# CanBus-Gartensteuerung.net
KiCad netlist of a schematic drawn in EAGLE
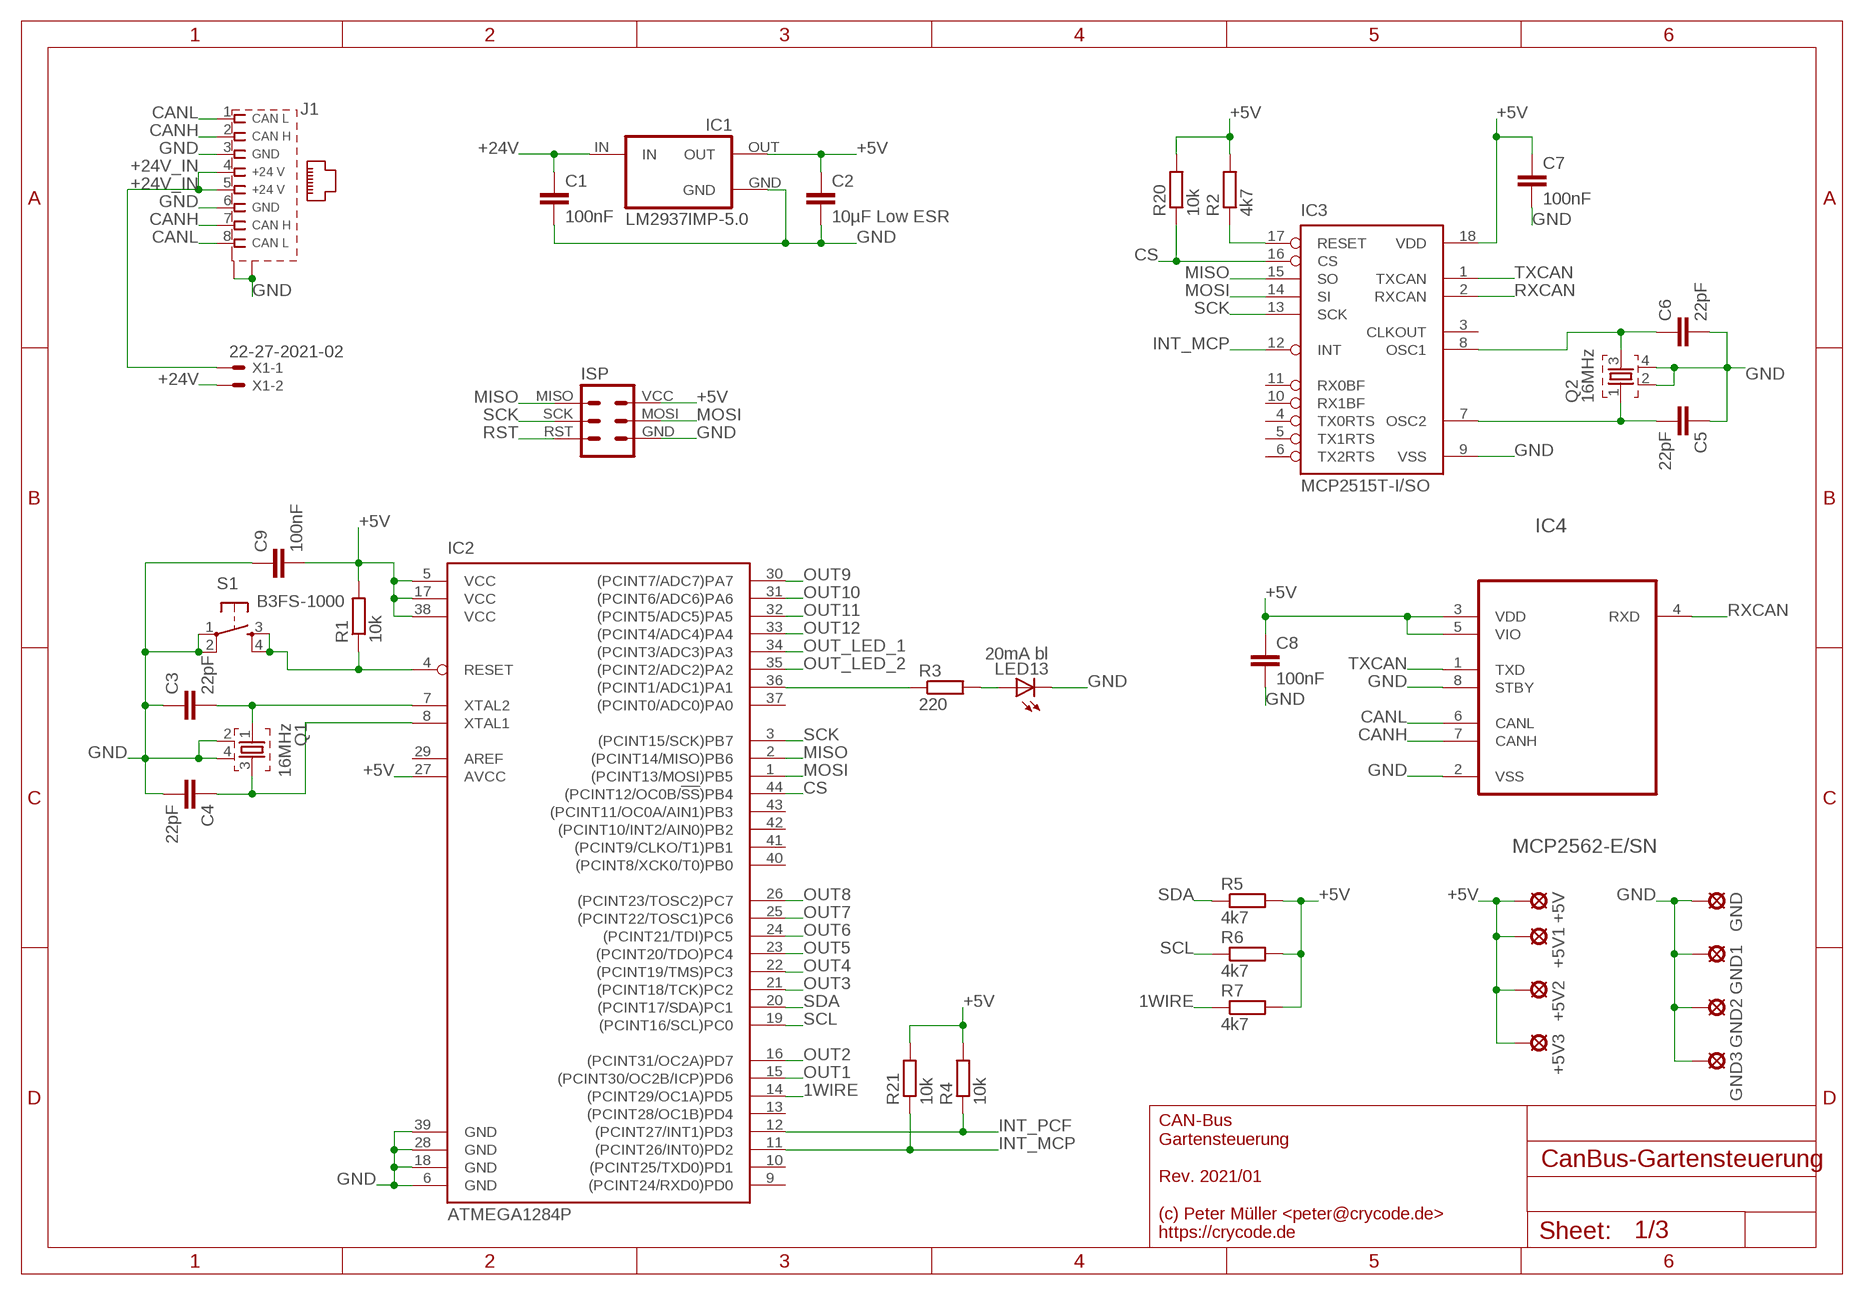
[diagram p0: schematic, sheet 1]
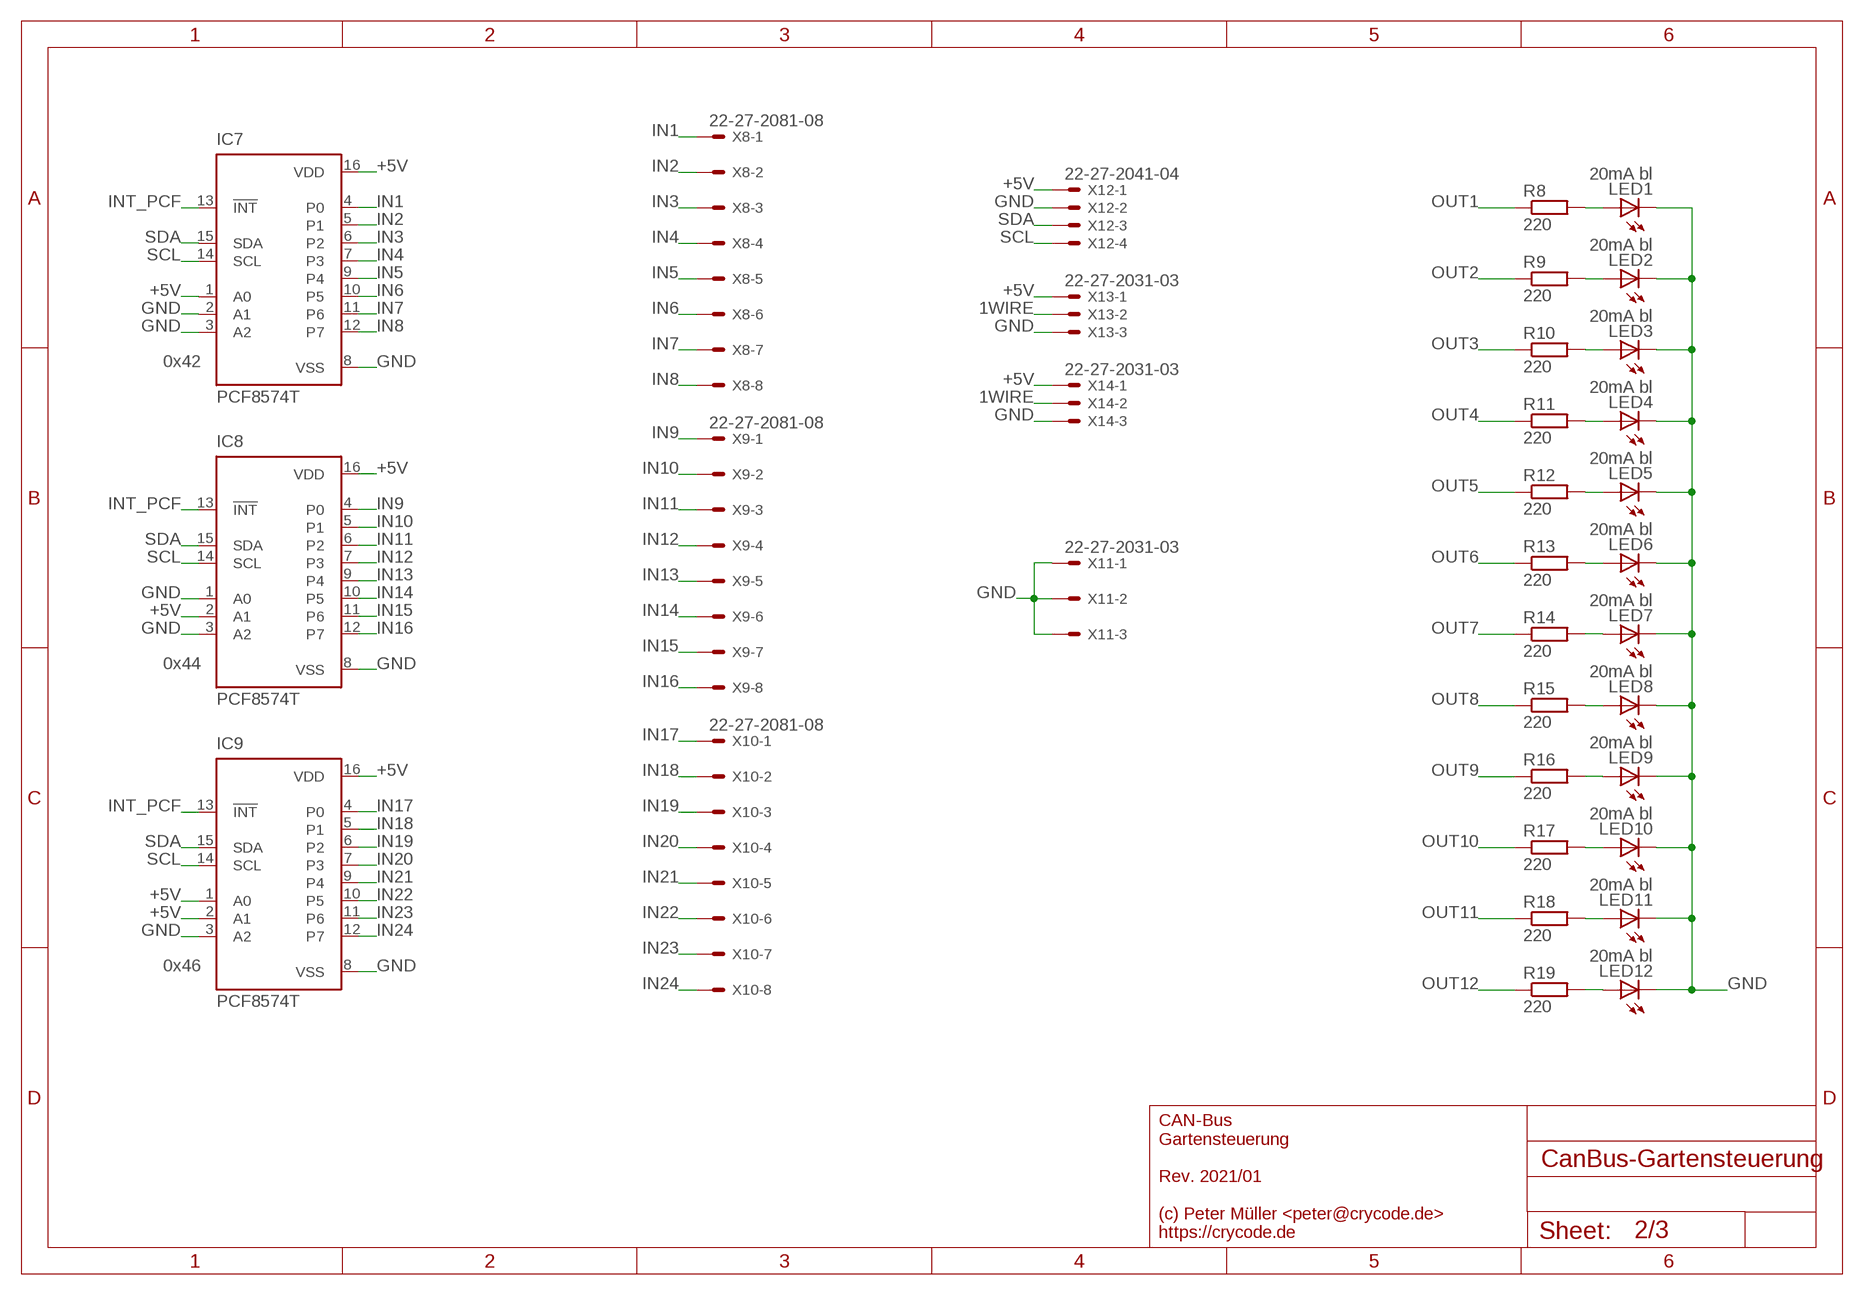
[diagram p1: schematic, sheet 2]
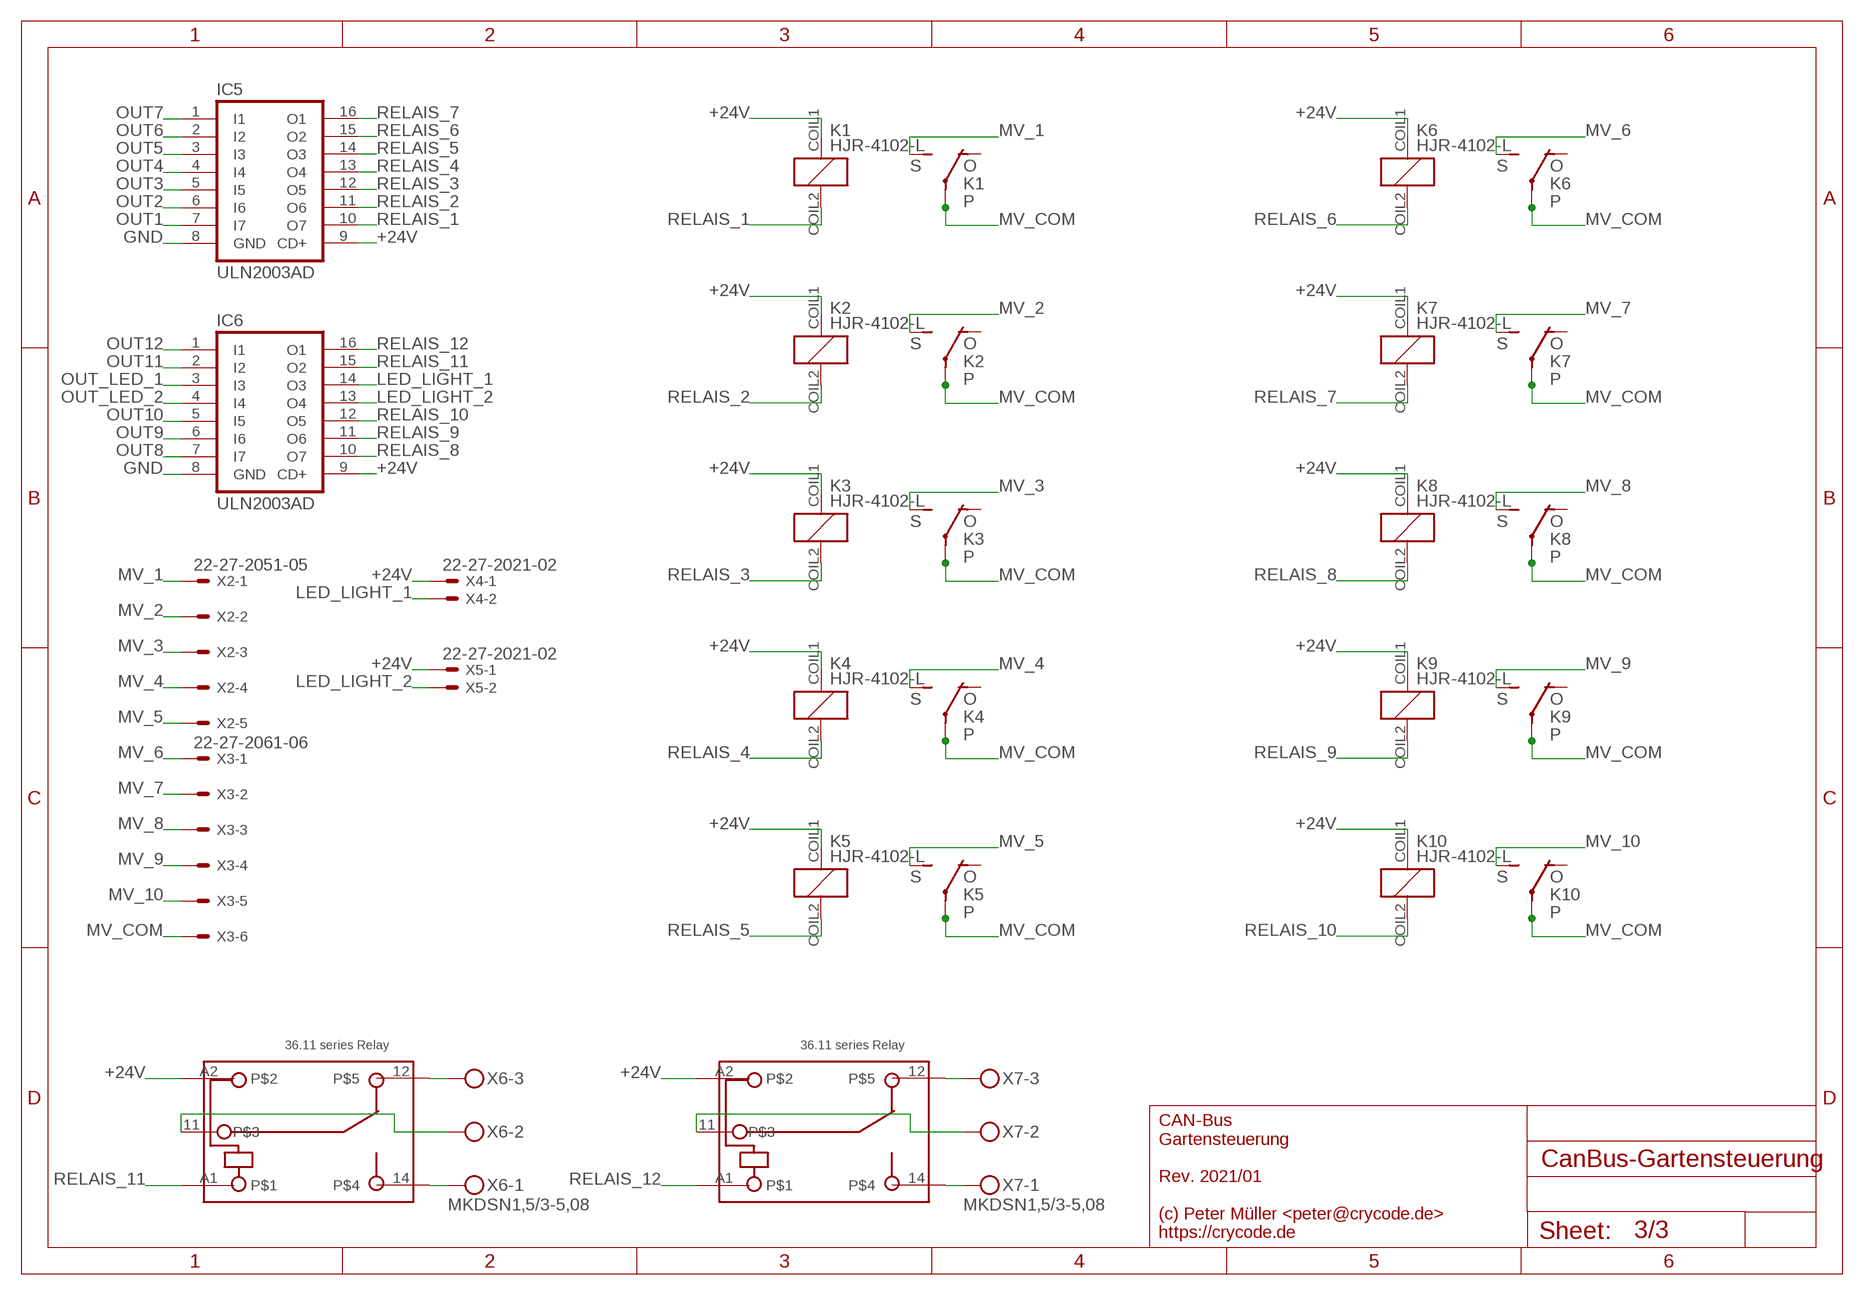
[diagram p2: schematic, sheet 3]

(export (version "E")
  (design (tool "Eeschema 10.0.6"))
  (components
    (comp (ref "+5V")
      (value "LSP13")
      (footprint "eagle-import:LSP13")
      (libsource (lib "eagle-import") (part "LSP13"))
    )
    (comp (ref "+5V1")
      (value "LSP13")
      (footprint "eagle-import:LSP13")
      (libsource (lib "eagle-import") (part "LSP13"))
    )
    (comp (ref "+5V2")
      (value "LSP13")
      (footprint "eagle-import:LSP13")
      (libsource (lib "eagle-import") (part "LSP13"))
    )
    (comp (ref "+5V3")
      (value "LSP13")
      (footprint "eagle-import:LSP13")
      (libsource (lib "eagle-import") (part "LSP13"))
    )
    (comp (ref "C1")
      (value "100nF")
      (footprint "eagle-import:C0805")
      (libsource (lib "eagle-import") (part "C-EUC0805"))
    )
    (comp (ref "C2")
      (value "10µF Low ESR")
      (footprint "eagle-import:C0805")
      (libsource (lib "eagle-import") (part "C-EUC0805"))
    )
    (comp (ref "C3")
      (value "22pF")
      (footprint "eagle-import:C0805")
      (libsource (lib "eagle-import") (part "C-EUC0805"))
    )
    (comp (ref "C4")
      (value "22pF")
      (footprint "eagle-import:C0805")
      (libsource (lib "eagle-import") (part "C-EUC0805"))
    )
    (comp (ref "C5")
      (value "22pF")
      (footprint "eagle-import:C0805")
      (libsource (lib "eagle-import") (part "C-EUC0805"))
    )
    (comp (ref "C6")
      (value "22pF")
      (footprint "eagle-import:C0805")
      (libsource (lib "eagle-import") (part "C-EUC0805"))
    )
    (comp (ref "C7")
      (value "100nF")
      (footprint "eagle-import:C0805")
      (libsource (lib "eagle-import") (part "C-EUC0805"))
    )
    (comp (ref "C8")
      (value "100nF")
      (footprint "eagle-import:C0805")
      (libsource (lib "eagle-import") (part "C-EUC0805"))
    )
    (comp (ref "C9")
      (value "100nF")
      (footprint "eagle-import:C0805")
      (libsource (lib "eagle-import") (part "C-EUC0805"))
    )
    (comp (ref "GND")
      (value "LSP13")
      (footprint "eagle-import:LSP13")
      (libsource (lib "eagle-import") (part "LSP13"))
    )
    (comp (ref "GND1")
      (value "LSP13")
      (footprint "eagle-import:LSP13")
      (libsource (lib "eagle-import") (part "LSP13"))
    )
    (comp (ref "GND2")
      (value "LSP13")
      (footprint "eagle-import:LSP13")
      (libsource (lib "eagle-import") (part "LSP13"))
    )
    (comp (ref "GND3")
      (value "LSP13")
      (footprint "eagle-import:LSP13")
      (libsource (lib "eagle-import") (part "LSP13"))
    )
    (comp (ref "IC1")
      (value "LM2937IMP-5.0")
      (footprint "eagle-import:SOT223")
      (libsource (lib "eagle-import") (part "LM2937IMP-5.0"))
    )
    (comp (ref "IC2")
      (value "ATMEGA1284P")
      (footprint "eagle-import:TQFP44")
      (fields (field (name "MPN") "ATMEGA644PV-10AU"))
      (libsource (lib "eagle-import") (part "ATMEGA644A"))
    )
    (comp (ref "IC3")
      (value "MCP2515T-I/SO")
      (footprint "eagle-import:SO18L")
      (libsource (lib "eagle-import") (part "MCP2515T-I/SO"))
    )
    (comp (ref "IC4")
      (value "MCP2562-E/SN")
      (footprint "eagle-import:SO08")
      (libsource (lib "eagle-import") (part "MCP2562-E/SN"))
    )
    (comp (ref "ISP")
      (value "ISPVIAS-ONLY-1.27MM")
      (footprint "eagle-import:ISP-VIAS-ONLY-1.27MM")
      (libsource (lib "eagle-import") (part "ISPVIAS-ONLY-1.27MM"))
    )
    (comp (ref "J1")
      (value "RJ45-CAN")
      (footprint "eagle-import:MEBP_8-8G")
      (libsource (lib "eagle-import") (part "RJ45-CAN"))
    )
    (comp (ref "LED13")
      (value "20mA bl")
      (footprint "eagle-import:CHIPLED_0805")
      (libsource (lib "eagle-import") (part "LEDCHIPLED_0805"))
    )
    (comp (ref "Q1")
      (value "16MHz")
      (footprint "eagle-import:MJ-5X3.2")
      (libsource (lib "eagle-import") (part "EUROQUARTZ-MMJ"))
    )
    (comp (ref "Q2")
      (value "16MHz")
      (footprint "eagle-import:MJ-5X3.2")
      (libsource (lib "eagle-import") (part "EUROQUARTZ-MMJ"))
    )
    (comp (ref "R1")
      (value "10k")
      (footprint "eagle-import:R0805")
      (libsource (lib "eagle-import") (part "R-EU_R0805"))
    )
    (comp (ref "R2")
      (value "4k7")
      (footprint "eagle-import:R0805")
      (libsource (lib "eagle-import") (part "R-EU_R0805"))
    )
    (comp (ref "R3")
      (value "220")
      (footprint "eagle-import:R0805")
      (libsource (lib "eagle-import") (part "R-EU_R0805"))
    )
    (comp (ref "R4")
      (value "10k")
      (footprint "eagle-import:R0805")
      (libsource (lib "eagle-import") (part "R-EU_R0805"))
    )
    (comp (ref "R5")
      (value "4k7")
      (footprint "eagle-import:R0805")
      (libsource (lib "eagle-import") (part "R-EU_R0805"))
    )
    (comp (ref "R6")
      (value "4k7")
      (footprint "eagle-import:R0805")
      (libsource (lib "eagle-import") (part "R-EU_R0805"))
    )
    (comp (ref "R7")
      (value "4k7")
      (footprint "eagle-import:R0805")
      (libsource (lib "eagle-import") (part "R-EU_R0805"))
    )
    (comp (ref "R20")
      (value "10k")
      (footprint "eagle-import:R0805")
      (libsource (lib "eagle-import") (part "R-EU_R0805"))
    )
    (comp (ref "R21")
      (value "10k")
      (footprint "eagle-import:R0805")
      (libsource (lib "eagle-import") (part "R-EU_R0805"))
    )
    (comp (ref "S1")
      (value "B3FS-1000")
      (footprint "eagle-import:B3FS-1000")
      (libsource (lib "eagle-import") (part "B3FS-1000"))
    )
    (comp (ref "X1")
      (value "22-27-2021-02")
      (footprint "eagle-import:6410-02")
      (libsource (lib "eagle-import") (part "22-?-0227-2021"))
    )
    (comp (ref "IC5")
      (value "ULN2003AD")
      (footprint "eagle-import:SO16")
      (libsource (lib "eagle-import") (part "ULN2003AD"))
    )
    (comp (ref "IC6")
      (value "ULN2003AD")
      (footprint "eagle-import:SO16")
      (libsource (lib "eagle-import") (part "ULN2003AD"))
    )
    (comp (ref "K1")
      (value "HJR-4102-L")
      (footprint "eagle-import:HJR4102")
      (libsource (lib "eagle-import") (part "HJR-4102-L"))
    )
    (comp (ref "K2")
      (value "HJR-4102-L")
      (footprint "eagle-import:HJR4102")
      (libsource (lib "eagle-import") (part "HJR-4102-L"))
    )
    (comp (ref "K3")
      (value "HJR-4102-L")
      (footprint "eagle-import:HJR4102")
      (libsource (lib "eagle-import") (part "HJR-4102-L"))
    )
    (comp (ref "K4")
      (value "HJR-4102-L")
      (footprint "eagle-import:HJR4102")
      (libsource (lib "eagle-import") (part "HJR-4102-L"))
    )
    (comp (ref "K5")
      (value "HJR-4102-L")
      (footprint "eagle-import:HJR4102")
      (libsource (lib "eagle-import") (part "HJR-4102-L"))
    )
    (comp (ref "K6")
      (value "HJR-4102-L")
      (footprint "eagle-import:HJR4102")
      (libsource (lib "eagle-import") (part "HJR-4102-L"))
    )
    (comp (ref "K7")
      (value "HJR-4102-L")
      (footprint "eagle-import:HJR4102")
      (libsource (lib "eagle-import") (part "HJR-4102-L"))
    )
    (comp (ref "K8")
      (value "HJR-4102-L")
      (footprint "eagle-import:HJR4102")
      (libsource (lib "eagle-import") (part "HJR-4102-L"))
    )
    (comp (ref "K9")
      (value "HJR-4102-L")
      (footprint "eagle-import:HJR4102")
      (libsource (lib "eagle-import") (part "HJR-4102-L"))
    )
    (comp (ref "K10")
      (value "HJR-4102-L")
      (footprint "eagle-import:HJR4102")
      (libsource (lib "eagle-import") (part "HJR-4102-L"))
    )
    (comp (ref "K11")
      (value "36.11")
      (footprint "eagle-import:36.11")
      (libsource (lib "eagle-import") (part "36.11"))
    )
    (comp (ref "K12")
      (value "36.11")
      (footprint "eagle-import:36.11")
      (libsource (lib "eagle-import") (part "36.11"))
    )
    (comp (ref "X2")
      (value "22-27-2051-05")
      (footprint "eagle-import:6410-05")
      (libsource (lib "eagle-import") (part "22-?-0527-2051"))
    )
    (comp (ref "X3")
      (value "22-27-2061-06")
      (footprint "eagle-import:6410-06")
      (libsource (lib "eagle-import") (part "22-?-0627-2061"))
    )
    (comp (ref "X4")
      (value "22-27-2021-02")
      (footprint "eagle-import:6410-02")
      (libsource (lib "eagle-import") (part "22-?-0227-2021"))
    )
    (comp (ref "X5")
      (value "22-27-2021-02")
      (footprint "eagle-import:6410-02")
      (libsource (lib "eagle-import") (part "22-?-0227-2021"))
    )
    (comp (ref "X6")
      (value "MKDSN1,5/3-5,08")
      (footprint "eagle-import:MKDSN1,5_3-5,08")
      (libsource (lib "eagle-import") (part "MKDSN1,5/3-5,08"))
    )
    (comp (ref "X7")
      (value "MKDSN1,5/3-5,08")
      (footprint "eagle-import:MKDSN1,5_3-5,08")
      (libsource (lib "eagle-import") (part "MKDSN1,5/3-5,08"))
    )
    (comp (ref "IC7")
      (value "PCF8574T")
      (footprint "eagle-import:SO16W")
      (fields (field (name "MPN") "PCF8574T/3,512"))
      (libsource (lib "eagle-import") (part "PCF8574T"))
    )
    (comp (ref "IC8")
      (value "PCF8574T")
      (footprint "eagle-import:SO16W")
      (fields (field (name "MPN") "PCF8574T/3,512"))
      (libsource (lib "eagle-import") (part "PCF8574T"))
    )
    (comp (ref "IC9")
      (value "PCF8574T")
      (footprint "eagle-import:SO16W")
      (fields (field (name "MPN") "PCF8574T/3,512"))
      (libsource (lib "eagle-import") (part "PCF8574T"))
    )
    (comp (ref "LED1")
      (value "20mA bl")
      (footprint "eagle-import:CHIPLED_0805")
      (libsource (lib "eagle-import") (part "LEDCHIPLED_0805"))
    )
    (comp (ref "LED2")
      (value "20mA bl")
      (footprint "eagle-import:CHIPLED_0805")
      (libsource (lib "eagle-import") (part "LEDCHIPLED_0805"))
    )
    (comp (ref "LED3")
      (value "20mA bl")
      (footprint "eagle-import:CHIPLED_0805")
      (libsource (lib "eagle-import") (part "LEDCHIPLED_0805"))
    )
    (comp (ref "LED4")
      (value "20mA bl")
      (footprint "eagle-import:CHIPLED_0805")
      (libsource (lib "eagle-import") (part "LEDCHIPLED_0805"))
    )
    (comp (ref "LED5")
      (value "20mA bl")
      (footprint "eagle-import:CHIPLED_0805")
      (libsource (lib "eagle-import") (part "LEDCHIPLED_0805"))
    )
    (comp (ref "LED6")
      (value "20mA bl")
      (footprint "eagle-import:CHIPLED_0805")
      (libsource (lib "eagle-import") (part "LEDCHIPLED_0805"))
    )
    (comp (ref "LED7")
      (value "20mA bl")
      (footprint "eagle-import:CHIPLED_0805")
      (libsource (lib "eagle-import") (part "LEDCHIPLED_0805"))
    )
    (comp (ref "LED8")
      (value "20mA bl")
      (footprint "eagle-import:CHIPLED_0805")
      (libsource (lib "eagle-import") (part "LEDCHIPLED_0805"))
    )
    (comp (ref "LED9")
      (value "20mA bl")
      (footprint "eagle-import:CHIPLED_0805")
      (libsource (lib "eagle-import") (part "LEDCHIPLED_0805"))
    )
    (comp (ref "LED10")
      (value "20mA bl")
      (footprint "eagle-import:CHIPLED_0805")
      (libsource (lib "eagle-import") (part "LEDCHIPLED_0805"))
    )
    (comp (ref "LED11")
      (value "20mA bl")
      (footprint "eagle-import:CHIPLED_0805")
      (libsource (lib "eagle-import") (part "LEDCHIPLED_0805"))
    )
    (comp (ref "LED12")
      (value "20mA bl")
      (footprint "eagle-import:CHIPLED_0805")
      (libsource (lib "eagle-import") (part "LEDCHIPLED_0805"))
    )
    (comp (ref "R8")
      (value "220")
      (footprint "eagle-import:R0805")
      (libsource (lib "eagle-import") (part "R-EU_R0805"))
    )
    (comp (ref "R9")
      (value "220")
      (footprint "eagle-import:R0805")
      (libsource (lib "eagle-import") (part "R-EU_R0805"))
    )
    (comp (ref "R10")
      (value "220")
      (footprint "eagle-import:R0805")
      (libsource (lib "eagle-import") (part "R-EU_R0805"))
    )
    (comp (ref "R11")
      (value "220")
      (footprint "eagle-import:R0805")
      (libsource (lib "eagle-import") (part "R-EU_R0805"))
    )
    (comp (ref "R12")
      (value "220")
      (footprint "eagle-import:R0805")
      (libsource (lib "eagle-import") (part "R-EU_R0805"))
    )
    (comp (ref "R13")
      (value "220")
      (footprint "eagle-import:R0805")
      (libsource (lib "eagle-import") (part "R-EU_R0805"))
    )
    (comp (ref "R14")
      (value "220")
      (footprint "eagle-import:R0805")
      (libsource (lib "eagle-import") (part "R-EU_R0805"))
    )
    (comp (ref "R15")
      (value "220")
      (footprint "eagle-import:R0805")
      (libsource (lib "eagle-import") (part "R-EU_R0805"))
    )
    (comp (ref "R16")
      (value "220")
      (footprint "eagle-import:R0805")
      (libsource (lib "eagle-import") (part "R-EU_R0805"))
    )
    (comp (ref "R17")
      (value "220")
      (footprint "eagle-import:R0805")
      (libsource (lib "eagle-import") (part "R-EU_R0805"))
    )
    (comp (ref "R18")
      (value "220")
      (footprint "eagle-import:R0805")
      (libsource (lib "eagle-import") (part "R-EU_R0805"))
    )
    (comp (ref "R19")
      (value "220")
      (footprint "eagle-import:R0805")
      (libsource (lib "eagle-import") (part "R-EU_R0805"))
    )
    (comp (ref "X8")
      (value "22-27-2081-08")
      (footprint "eagle-import:6410-08")
      (libsource (lib "eagle-import") (part "22-?-0827-2081"))
    )
    (comp (ref "X9")
      (value "22-27-2081-08")
      (footprint "eagle-import:6410-08")
      (libsource (lib "eagle-import") (part "22-?-0827-2081"))
    )
    (comp (ref "X10")
      (value "22-27-2081-08")
      (footprint "eagle-import:6410-08")
      (libsource (lib "eagle-import") (part "22-?-0827-2081"))
    )
    (comp (ref "X11")
      (value "22-27-2031-03")
      (footprint "eagle-import:6410-03")
      (libsource (lib "eagle-import") (part "22-?-0327-2031"))
    )
    (comp (ref "X12")
      (value "22-27-2041-04")
      (footprint "eagle-import:6410-04")
      (libsource (lib "eagle-import") (part "22-?-0427-2041"))
    )
    (comp (ref "X13")
      (value "22-27-2031-03")
      (footprint "eagle-import:6410-03")
      (libsource (lib "eagle-import") (part "22-?-0327-2031"))
    )
    (comp (ref "X14")
      (value "22-27-2031-03")
      (footprint "eagle-import:6410-03")
      (libsource (lib "eagle-import") (part "22-?-0327-2031"))
    )
  )
  (nets
    (net (code "1") (name "+5V") (class "Default")
      (node (ref "+5V") (pin "MP") (pinfunction "MP_MP") (pintype "passive"))
      (node (ref "+5V1") (pin "MP") (pinfunction "MP_MP") (pintype "passive"))
      (node (ref "+5V2") (pin "MP") (pinfunction "MP_MP") (pintype "passive"))
      (node (ref "+5V3") (pin "MP") (pinfunction "MP_MP") (pintype "passive"))
      (node (ref "C2") (pin "1") (pinfunction "1_1") (pintype "passive"))
      (node (ref "C7") (pin "1") (pinfunction "1_1") (pintype "passive"))
      (node (ref "C8") (pin "1") (pinfunction "1_1") (pintype "passive"))
      (node (ref "C9") (pin "2") (pinfunction "2_2") (pintype "passive"))
      (node (ref "IC1") (pin "OUT") (pinfunction "OUT_OUT") (pintype "output"))
      (node (ref "IC2") (pin "17") (pinfunction "VCC_17") (pintype "power_in"))
      (node (ref "IC2") (pin "27") (pinfunction "AVCC_27") (pintype "power_in"))
      (node (ref "IC2") (pin "38") (pinfunction "VCC_38") (pintype "power_in"))
      (node (ref "IC2") (pin "5") (pinfunction "VCC_5") (pintype "power_in"))
      (node (ref "IC3") (pin "18") (pinfunction "VDD_18") (pintype "power_in"))
      (node (ref "IC4") (pin "3") (pinfunction "VDD_3") (pintype "power_in"))
      (node (ref "IC4") (pin "5") (pinfunction "VIO_5") (pintype "power_in"))
      (node (ref "IC7") (pin "1") (pinfunction "A0_1") (pintype "input"))
      (node (ref "IC7") (pin "16") (pinfunction "VDD_16") (pintype "power_in"))
      (node (ref "IC8") (pin "16") (pinfunction "VDD_16") (pintype "power_in"))
      (node (ref "IC8") (pin "2") (pinfunction "A1_2") (pintype "input"))
      (node (ref "IC9") (pin "1") (pinfunction "A0_1") (pintype "input"))
      (node (ref "IC9") (pin "16") (pinfunction "VDD_16") (pintype "power_in"))
      (node (ref "IC9") (pin "2") (pinfunction "A1_2") (pintype "input"))
      (node (ref "ISP") (pin "VCC") (pinfunction "VCC_VCC") (pintype "passive"))
      (node (ref "R1") (pin "2") (pinfunction "2_2") (pintype "passive"))
      (node (ref "R2") (pin "2") (pinfunction "2_2") (pintype "passive"))
      (node (ref "R20") (pin "2") (pinfunction "2_2") (pintype "passive"))
      (node (ref "R21") (pin "2") (pinfunction "2_2") (pintype "passive"))
      (node (ref "R4") (pin "2") (pinfunction "2_2") (pintype "passive"))
      (node (ref "R5") (pin "2") (pinfunction "2_2") (pintype "passive"))
      (node (ref "R6") (pin "2") (pinfunction "2_2") (pintype "passive"))
      (node (ref "R7") (pin "2") (pinfunction "2_2") (pintype "passive"))
      (node (ref "X12") (pin "1") (pinfunction "S_1") (pintype "passive"))
      (node (ref "X13") (pin "1") (pinfunction "S_1") (pintype "passive"))
      (node (ref "X14") (pin "1") (pinfunction "S_1") (pintype "passive"))
    )
    (net (code "2") (name "+24V") (class "Default")
      (node (ref "C1") (pin "1") (pinfunction "1_1") (pintype "passive"))
      (node (ref "IC1") (pin "IN") (pinfunction "IN_IN") (pintype "input"))
      (node (ref "IC5") (pin "9") (pinfunction "CD+_9") (pintype "passive"))
      (node (ref "IC6") (pin "9") (pinfunction "CD+_9") (pintype "passive"))
      (node (ref "K1") (pin "COIL1") (pinfunction "1_COIL1") (pintype "passive"))
      (node (ref "K10") (pin "COIL1") (pinfunction "1_COIL1") (pintype "passive"))
      (node (ref "K11") (pin "A2") (pinfunction "P$2_A2") (pintype "passive"))
      (node (ref "K12") (pin "A2") (pinfunction "P$2_A2") (pintype "passive"))
      (node (ref "K2") (pin "COIL1") (pinfunction "1_COIL1") (pintype "passive"))
      (node (ref "K3") (pin "COIL1") (pinfunction "1_COIL1") (pintype "passive"))
      (node (ref "K4") (pin "COIL1") (pinfunction "1_COIL1") (pintype "passive"))
      (node (ref "K5") (pin "COIL1") (pinfunction "1_COIL1") (pintype "passive"))
      (node (ref "K6") (pin "COIL1") (pinfunction "1_COIL1") (pintype "passive"))
      (node (ref "K7") (pin "COIL1") (pinfunction "1_COIL1") (pintype "passive"))
      (node (ref "K8") (pin "COIL1") (pinfunction "1_COIL1") (pintype "passive"))
      (node (ref "K9") (pin "COIL1") (pinfunction "1_COIL1") (pintype "passive"))
      (node (ref "X1") (pin "2") (pinfunction "S_2") (pintype "passive"))
      (node (ref "X4") (pin "1") (pinfunction "S_1") (pintype "passive"))
      (node (ref "X5") (pin "1") (pinfunction "S_1") (pintype "passive"))
    )
    (net (code "3") (name "+24V_IN") (class "Default")
      (node (ref "J1") (pin "4") (pinfunction "4_4") (pintype "passive"))
      (node (ref "J1") (pin "5") (pinfunction "5_5") (pintype "passive"))
      (node (ref "X1") (pin "1") (pinfunction "S_1") (pintype "passive"))
    )
    (net (code "4") (name "1WIRE") (class "Default")
      (node (ref "IC2") (pin "14") (pinfunction "(PCINT29/OC1A)PD5_14") (pintype "bidirectional"))
      (node (ref "R7") (pin "1") (pinfunction "1_1") (pintype "passive"))
      (node (ref "X13") (pin "2") (pinfunction "S_2") (pintype "passive"))
      (node (ref "X14") (pin "2") (pinfunction "S_2") (pintype "passive"))
    )
    (net (code "5") (name "CANH") (class "Default")
      (node (ref "IC4") (pin "7") (pinfunction "CANH_7") (pintype "bidirectional"))
      (node (ref "J1") (pin "2") (pinfunction "2_2") (pintype "passive"))
      (node (ref "J1") (pin "7") (pinfunction "7_7") (pintype "passive"))
    )
    (net (code "6") (name "CANL") (class "Default")
      (node (ref "IC4") (pin "6") (pinfunction "CANL_6") (pintype "bidirectional"))
      (node (ref "J1") (pin "1") (pinfunction "1_1") (pintype "passive"))
      (node (ref "J1") (pin "8") (pinfunction "8_8") (pintype "passive"))
    )
    (net (code "7") (name "CS") (class "Default")
      (node (ref "IC2") (pin "44") (pinfunction "(PCINT12/OC0B/~{SS})PB4_44") (pintype "bidirectional"))
      (node (ref "IC3") (pin "16") (pinfunction "CS_16") (pintype "input"))
      (node (ref "R20") (pin "1") (pinfunction "1_1") (pintype "passive"))
    )
    (net (code "8") (name "GND") (class "Default")
      (node (ref "C1") (pin "2") (pinfunction "2_2") (pintype "passive"))
      (node (ref "C2") (pin "2") (pinfunction "2_2") (pintype "passive"))
      (node (ref "C3") (pin "1") (pinfunction "1_1") (pintype "passive"))
      (node (ref "C4") (pin "2") (pinfunction "2_2") (pintype "passive"))
      (node (ref "C5") (pin "1") (pinfunction "1_1") (pintype "passive"))
      (node (ref "C6") (pin "2") (pinfunction "2_2") (pintype "passive"))
      (node (ref "C7") (pin "2") (pinfunction "2_2") (pintype "passive"))
      (node (ref "C8") (pin "2") (pinfunction "2_2") (pintype "passive"))
      (node (ref "C9") (pin "1") (pinfunction "1_1") (pintype "passive"))
      (node (ref "GND") (pin "MP") (pinfunction "MP_MP") (pintype "passive"))
      (node (ref "GND1") (pin "MP") (pinfunction "MP_MP") (pintype "passive"))
      (node (ref "GND2") (pin "MP") (pinfunction "MP_MP") (pintype "passive"))
      (node (ref "GND3") (pin "MP") (pinfunction "MP_MP") (pintype "passive"))
      (node (ref "IC1") (pin "GND") (pinfunction "GND_GND") (pintype "power_in"))
      (node (ref "IC2") (pin "18") (pinfunction "GND_18") (pintype "power_in"))
      (node (ref "IC2") (pin "28") (pinfunction "GND_28") (pintype "power_in"))
      (node (ref "IC2") (pin "39") (pinfunction "GND_39") (pintype "power_in"))
      (node (ref "IC2") (pin "6") (pinfunction "GND_6") (pintype "power_in"))
      (node (ref "IC3") (pin "9") (pinfunction "VSS_9") (pintype "power_in"))
      (node (ref "IC4") (pin "2") (pinfunction "VSS_2") (pintype "power_in"))
      (node (ref "IC4") (pin "8") (pinfunction "STBY_8") (pintype "input"))
      (node (ref "IC5") (pin "8") (pinfunction "GND_8") (pintype "power_in"))
      (node (ref "IC6") (pin "8") (pinfunction "GND_8") (pintype "power_in"))
      (node (ref "IC7") (pin "2") (pinfunction "A1_2") (pintype "input"))
      (node (ref "IC7") (pin "3") (pinfunction "A2_3") (pintype "input"))
      (node (ref "IC7") (pin "8") (pinfunction "VSS_8") (pintype "power_in"))
      (node (ref "IC8") (pin "1") (pinfunction "A0_1") (pintype "input"))
      (node (ref "IC8") (pin "3") (pinfunction "A2_3") (pintype "input"))
      (node (ref "IC8") (pin "8") (pinfunction "VSS_8") (pintype "power_in"))
      (node (ref "IC9") (pin "3") (pinfunction "A2_3") (pintype "input"))
      (node (ref "IC9") (pin "8") (pinfunction "VSS_8") (pintype "power_in"))
      (node (ref "ISP") (pin "GND") (pinfunction "GND_GND") (pintype "passive"))
      (node (ref "J1") (pin "3") (pinfunction "3_3") (pintype "passive"))
      (node (ref "J1") (pin "6") (pinfunction "6_6") (pintype "passive"))
      (node (ref "J1") (pin "G1") (pinfunction "S1_G1") (pintype "passive"))
      (node (ref "J1") (pin "G2") (pinfunction "S2_G2") (pintype "passive"))
      (node (ref "LED1") (pin "C") (pinfunction "C_C") (pintype "passive"))
      (node (ref "LED10") (pin "C") (pinfunction "C_C") (pintype "passive"))
      (node (ref "LED11") (pin "C") (pinfunction "C_C") (pintype "passive"))
      (node (ref "LED12") (pin "C") (pinfunction "C_C") (pintype "passive"))
      (node (ref "LED13") (pin "C") (pinfunction "C_C") (pintype "passive"))
      (node (ref "LED2") (pin "C") (pinfunction "C_C") (pintype "passive"))
      (node (ref "LED3") (pin "C") (pinfunction "C_C") (pintype "passive"))
      (node (ref "LED4") (pin "C") (pinfunction "C_C") (pintype "passive"))
      (node (ref "LED5") (pin "C") (pinfunction "C_C") (pintype "passive"))
      (node (ref "LED6") (pin "C") (pinfunction "C_C") (pintype "passive"))
      (node (ref "LED7") (pin "C") (pinfunction "C_C") (pintype "passive"))
      (node (ref "LED8") (pin "C") (pinfunction "C_C") (pintype "passive"))
      (node (ref "LED9") (pin "C") (pinfunction "C_C") (pintype "passive"))
      (node (ref "Q1") (pin "2") (pinfunction "2_2") (pintype "passive"))
      (node (ref "Q1") (pin "4") (pinfunction "4_4") (pintype "passive"))
      (node (ref "Q2") (pin "2") (pinfunction "2_2") (pintype "passive"))
      (node (ref "Q2") (pin "4") (pinfunction "4_4") (pintype "passive"))
      (node (ref "S1") (pin "1") (pinfunction "P_1") (pintype "passive"))
      (node (ref "S1") (pin "2") (pinfunction "P1_2") (pintype "passive"))
      (node (ref "X11") (pin "1") (pinfunction "S_1") (pintype "passive"))
      (node (ref "X11") (pin "2") (pinfunction "S_2") (pintype "passive"))
      (node (ref "X11") (pin "3") (pinfunction "S_3") (pintype "passive"))
      (node (ref "X12") (pin "2") (pinfunction "S_2") (pintype "passive"))
      (node (ref "X13") (pin "3") (pinfunction "S_3") (pintype "passive"))
      (node (ref "X14") (pin "3") (pinfunction "S_3") (pintype "passive"))
    )
    (net (code "9") (name "IN1") (class "Default")
      (node (ref "IC7") (pin "4") (pinfunction "P0_4") (pintype "bidirectional"))
      (node (ref "X8") (pin "1") (pinfunction "S_1") (pintype "passive"))
    )
    (net (code "10") (name "IN2") (class "Default")
      (node (ref "IC7") (pin "5") (pinfunction "P1_5") (pintype "bidirectional"))
      (node (ref "X8") (pin "2") (pinfunction "S_2") (pintype "passive"))
    )
    (net (code "11") (name "IN3") (class "Default")
      (node (ref "IC7") (pin "6") (pinfunction "P2_6") (pintype "bidirectional"))
      (node (ref "X8") (pin "3") (pinfunction "S_3") (pintype "passive"))
    )
    (net (code "12") (name "IN4") (class "Default")
      (node (ref "IC7") (pin "7") (pinfunction "P3_7") (pintype "bidirectional"))
      (node (ref "X8") (pin "4") (pinfunction "S_4") (pintype "passive"))
    )
    (net (code "13") (name "IN5") (class "Default")
      (node (ref "IC7") (pin "9") (pinfunction "P4_9") (pintype "bidirectional"))
      (node (ref "X8") (pin "5") (pinfunction "S_5") (pintype "passive"))
    )
    (net (code "14") (name "IN6") (class "Default")
      (node (ref "IC7") (pin "10") (pinfunction "P5_10") (pintype "bidirectional"))
      (node (ref "X8") (pin "6") (pinfunction "S_6") (pintype "passive"))
    )
    (net (code "15") (name "IN7") (class "Default")
      (node (ref "IC7") (pin "11") (pinfunction "P6_11") (pintype "bidirectional"))
      (node (ref "X8") (pin "7") (pinfunction "S_7") (pintype "passive"))
    )
    (net (code "16") (name "IN8") (class "Default")
      (node (ref "IC7") (pin "12") (pinfunction "P7_12") (pintype "bidirectional"))
      (node (ref "X8") (pin "8") (pinfunction "S_8") (pintype "passive"))
    )
    (net (code "17") (name "IN9") (class "Default")
      (node (ref "IC8") (pin "4") (pinfunction "P0_4") (pintype "bidirectional"))
      (node (ref "X9") (pin "1") (pinfunction "S_1") (pintype "passive"))
    )
    (net (code "18") (name "IN10") (class "Default")
      (node (ref "IC8") (pin "5") (pinfunction "P1_5") (pintype "bidirectional"))
      (node (ref "X9") (pin "2") (pinfunction "S_2") (pintype "passive"))
    )
    (net (code "19") (name "IN11") (class "Default")
      (node (ref "IC8") (pin "6") (pinfunction "P2_6") (pintype "bidirectional"))
      (node (ref "X9") (pin "3") (pinfunction "S_3") (pintype "passive"))
    )
    (net (code "20") (name "IN12") (class "Default")
      (node (ref "IC8") (pin "7") (pinfunction "P3_7") (pintype "bidirectional"))
      (node (ref "X9") (pin "4") (pinfunction "S_4") (pintype "passive"))
    )
    (net (code "21") (name "IN13") (class "Default")
      (node (ref "IC8") (pin "9") (pinfunction "P4_9") (pintype "bidirectional"))
      (node (ref "X9") (pin "5") (pinfunction "S_5") (pintype "passive"))
    )
    (net (code "22") (name "IN14") (class "Default")
      (node (ref "IC8") (pin "10") (pinfunction "P5_10") (pintype "bidirectional"))
      (node (ref "X9") (pin "6") (pinfunction "S_6") (pintype "passive"))
    )
    (net (code "23") (name "IN15") (class "Default")
      (node (ref "IC8") (pin "11") (pinfunction "P6_11") (pintype "bidirectional"))
      (node (ref "X9") (pin "7") (pinfunction "S_7") (pintype "passive"))
    )
    (net (code "24") (name "IN16") (class "Default")
      (node (ref "IC8") (pin "12") (pinfunction "P7_12") (pintype "bidirectional"))
      (node (ref "X9") (pin "8") (pinfunction "S_8") (pintype "passive"))
    )
    (net (code "25") (name "IN17") (class "Default")
      (node (ref "IC9") (pin "4") (pinfunction "P0_4") (pintype "bidirectional"))
      (node (ref "X10") (pin "1") (pinfunction "S_1") (pintype "passive"))
    )
    (net (code "26") (name "IN18") (class "Default")
      (node (ref "IC9") (pin "5") (pinfunction "P1_5") (pintype "bidirectional"))
      (node (ref "X10") (pin "2") (pinfunction "S_2") (pintype "passive"))
    )
    (net (code "27") (name "IN19") (class "Default")
      (node (ref "IC9") (pin "6") (pinfunction "P2_6") (pintype "bidirectional"))
      (node (ref "X10") (pin "3") (pinfunction "S_3") (pintype "passive"))
    )
    (net (code "28") (name "IN20") (class "Default")
      (node (ref "IC9") (pin "7") (pinfunction "P3_7") (pintype "bidirectional"))
      (node (ref "X10") (pin "4") (pinfunction "S_4") (pintype "passive"))
    )
    (net (code "29") (name "IN21") (class "Default")
      (node (ref "IC9") (pin "9") (pinfunction "P4_9") (pintype "bidirectional"))
      (node (ref "X10") (pin "5") (pinfunction "S_5") (pintype "passive"))
    )
    (net (code "30") (name "IN22") (class "Default")
      (node (ref "IC9") (pin "10") (pinfunction "P5_10") (pintype "bidirectional"))
      (node (ref "X10") (pin "6") (pinfunction "S_6") (pintype "passive"))
    )
    (net (code "31") (name "IN23") (class "Default")
      (node (ref "IC9") (pin "11") (pinfunction "P6_11") (pintype "bidirectional"))
      (node (ref "X10") (pin "7") (pinfunction "S_7") (pintype "passive"))
    )
    (net (code "32") (name "IN24") (class "Default")
      (node (ref "IC9") (pin "12") (pinfunction "P7_12") (pintype "bidirectional"))
      (node (ref "X10") (pin "8") (pinfunction "S_8") (pintype "passive"))
    )
    (net (code "33") (name "INT_MCP") (class "Default")
      (node (ref "IC2") (pin "11") (pinfunction "(PCINT26/INT0)PD2_11") (pintype "bidirectional"))
      (node (ref "IC3") (pin "12") (pinfunction "INT_12") (pintype "output"))
      (node (ref "R21") (pin "1") (pinfunction "1_1") (pintype "passive"))
    )
    (net (code "34") (name "INT_PCF") (class "Default")
      (node (ref "IC2") (pin "12") (pinfunction "(PCINT27/INT1)PD3_12") (pintype "bidirectional"))
      (node (ref "IC7") (pin "13") (pinfunction "~{INT}_13") (pintype "output"))
      (node (ref "IC8") (pin "13") (pinfunction "~{INT}_13") (pintype "output"))
      (node (ref "IC9") (pin "13") (pinfunction "~{INT}_13") (pintype "output"))
      (node (ref "R4") (pin "1") (pinfunction "1_1") (pintype "passive"))
    )
    (net (code "35") (name "LED_LIGHT_1") (class "Default")
      (node (ref "IC6") (pin "14") (pinfunction "O3_14") (pintype "open_collector"))
      (node (ref "X4") (pin "2") (pinfunction "S_2") (pintype "passive"))
    )
    (net (code "36") (name "LED_LIGHT_2") (class "Default")
      (node (ref "IC6") (pin "13") (pinfunction "O4_13") (pintype "open_collector"))
      (node (ref "X5") (pin "2") (pinfunction "S_2") (pintype "passive"))
    )
    (net (code "37") (name "MISO") (class "Default")
      (node (ref "IC2") (pin "2") (pinfunction "(PCINT14/MISO)PB6_2") (pintype "bidirectional"))
      (node (ref "IC3") (pin "15") (pinfunction "SO_15") (pintype "output"))
      (node (ref "ISP") (pin "MISO") (pinfunction "MISO_MISO") (pintype "passive"))
    )
    (net (code "38") (name "MOSI") (class "Default")
      (node (ref "IC2") (pin "1") (pinfunction "(PCINT13/MOSI)PB5_1") (pintype "bidirectional"))
      (node (ref "IC3") (pin "14") (pinfunction "SI_14") (pintype "input"))
      (node (ref "ISP") (pin "MOSI") (pinfunction "MOSI_MOSI") (pintype "passive"))
    )
    (net (code "39") (name "MV_1") (class "Default")
      (node (ref "K1") (pin "CON1DEFAULT") (pinfunction "S_CON1DEFAULT") (pintype "passive"))
      (node (ref "X2") (pin "1") (pinfunction "S_1") (pintype "passive"))
    )
    (net (code "40") (name "MV_2") (class "Default")
      (node (ref "K2") (pin "CON1DEFAULT") (pinfunction "S_CON1DEFAULT") (pintype "passive"))
      (node (ref "X2") (pin "2") (pinfunction "S_2") (pintype "passive"))
    )
    (net (code "41") (name "MV_3") (class "Default")
      (node (ref "K3") (pin "CON1DEFAULT") (pinfunction "S_CON1DEFAULT") (pintype "passive"))
      (node (ref "X2") (pin "3") (pinfunction "S_3") (pintype "passive"))
    )
    (net (code "42") (name "MV_4") (class "Default")
      (node (ref "K4") (pin "CON1DEFAULT") (pinfunction "S_CON1DEFAULT") (pintype "passive"))
      (node (ref "X2") (pin "4") (pinfunction "S_4") (pintype "passive"))
    )
    (net (code "43") (name "MV_5") (class "Default")
      (node (ref "K5") (pin "CON1DEFAULT") (pinfunction "S_CON1DEFAULT") (pintype "passive"))
      (node (ref "X2") (pin "5") (pinfunction "S_5") (pintype "passive"))
    )
    (net (code "44") (name "MV_6") (class "Default")
      (node (ref "K6") (pin "CON1DEFAULT") (pinfunction "S_CON1DEFAULT") (pintype "passive"))
      (node (ref "X3") (pin "1") (pinfunction "S_1") (pintype "passive"))
    )
    (net (code "45") (name "MV_7") (class "Default")
      (node (ref "K7") (pin "CON1DEFAULT") (pinfunction "S_CON1DEFAULT") (pintype "passive"))
      (node (ref "X3") (pin "2") (pinfunction "S_2") (pintype "passive"))
    )
    (net (code "46") (name "MV_8") (class "Default")
      (node (ref "K8") (pin "CON1DEFAULT") (pinfunction "S_CON1DEFAULT") (pintype "passive"))
      (node (ref "X3") (pin "3") (pinfunction "S_3") (pintype "passive"))
    )
    (net (code "47") (name "MV_9") (class "Default")
      (node (ref "K9") (pin "CON1DEFAULT") (pinfunction "S_CON1DEFAULT") (pintype "passive"))
      (node (ref "X3") (pin "4") (pinfunction "S_4") (pintype "passive"))
    )
    (net (code "48") (name "MV_10") (class "Default")
      (node (ref "K10") (pin "CON1DEFAULT") (pinfunction "S_CON1DEFAULT") (pintype "passive"))
      (node (ref "X3") (pin "5") (pinfunction "S_5") (pintype "passive"))
    )
    (net (code "49") (name "MV_COM") (class "Default")
      (node (ref "K1") (pin "CENTER1") (pinfunction "P_CENTER1") (pintype "passive"))
      (node (ref "K1") (pin "CENTER2") (pinfunction "P2_CENTER2") (pintype "bidirectional"))
      (node (ref "K10") (pin "CENTER1") (pinfunction "P_CENTER1") (pintype "passive"))
      (node (ref "K10") (pin "CENTER2") (pinfunction "P2_CENTER2") (pintype "bidirectional"))
      (node (ref "K2") (pin "CENTER1") (pinfunction "P_CENTER1") (pintype "passive"))
      (node (ref "K2") (pin "CENTER2") (pinfunction "P2_CENTER2") (pintype "bidirectional"))
      (node (ref "K3") (pin "CENTER1") (pinfunction "P_CENTER1") (pintype "passive"))
      (node (ref "K3") (pin "CENTER2") (pinfunction "P2_CENTER2") (pintype "bidirectional"))
      (node (ref "K4") (pin "CENTER1") (pinfunction "P_CENTER1") (pintype "passive"))
      (node (ref "K4") (pin "CENTER2") (pinfunction "P2_CENTER2") (pintype "bidirectional"))
      (node (ref "K5") (pin "CENTER1") (pinfunction "P_CENTER1") (pintype "passive"))
      (node (ref "K5") (pin "CENTER2") (pinfunction "P2_CENTER2") (pintype "bidirectional"))
      (node (ref "K6") (pin "CENTER1") (pinfunction "P_CENTER1") (pintype "passive"))
      (node (ref "K6") (pin "CENTER2") (pinfunction "P2_CENTER2") (pintype "bidirectional"))
      (node (ref "K7") (pin "CENTER1") (pinfunction "P_CENTER1") (pintype "passive"))
      (node (ref "K7") (pin "CENTER2") (pinfunction "P2_CENTER2") (pintype "bidirectional"))
      (node (ref "K8") (pin "CENTER1") (pinfunction "P_CENTER1") (pintype "passive"))
      (node (ref "K8") (pin "CENTER2") (pinfunction "P2_CENTER2") (pintype "bidirectional"))
      (node (ref "K9") (pin "CENTER1") (pinfunction "P_CENTER1") (pintype "passive"))
      (node (ref "K9") (pin "CENTER2") (pinfunction "P2_CENTER2") (pintype "bidirectional"))
      (node (ref "X3") (pin "6") (pinfunction "S_6") (pintype "passive"))
    )
    (net (code "50") (name "Net-(IC2-(PCINT1{slash}ADC1)PA1)") (class "Default")
      (node (ref "IC2") (pin "36") (pinfunction "(PCINT1/ADC1)PA1_36") (pintype "bidirectional"))
      (node (ref "R3") (pin "1") (pinfunction "1_1") (pintype "passive"))
    )
    (net (code "51") (name "Net-(IC2-XTAL1)") (class "Default")
      (node (ref "C4") (pin "1") (pinfunction "1_1") (pintype "passive"))
      (node (ref "IC2") (pin "8") (pinfunction "XTAL1_8") (pintype "bidirectional"))
      (node (ref "Q1") (pin "3") (pinfunction "3_3") (pintype "passive"))
    )
    (net (code "52") (name "Net-(IC2-XTAL2)") (class "Default")
      (node (ref "C3") (pin "2") (pinfunction "2_2") (pintype "passive"))
      (node (ref "IC2") (pin "7") (pinfunction "XTAL2_7") (pintype "bidirectional"))
      (node (ref "Q1") (pin "1") (pinfunction "1_1") (pintype "passive"))
    )
    (net (code "53") (name "Net-(IC3-OSC1)") (class "Default")
      (node (ref "C6") (pin "1") (pinfunction "1_1") (pintype "passive"))
      (node (ref "IC3") (pin "8") (pinfunction "OSC1_8") (pintype "input"))
      (node (ref "Q2") (pin "3") (pinfunction "3_3") (pintype "passive"))
    )
    (net (code "54") (name "Net-(IC3-OSC2)") (class "Default")
      (node (ref "C5") (pin "2") (pinfunction "2_2") (pintype "passive"))
      (node (ref "IC3") (pin "7") (pinfunction "OSC2_7") (pintype "output"))
      (node (ref "Q2") (pin "1") (pinfunction "1_1") (pintype "passive"))
    )
    (net (code "55") (name "Net-(IC3-RESET)") (class "Default")
      (node (ref "IC3") (pin "17") (pinfunction "RESET_17") (pintype "input"))
      (node (ref "R2") (pin "1") (pinfunction "1_1") (pintype "passive"))
    )
    (net (code "56") (name "Net-(K11-P$3)") (class "Default")
      (node (ref "K11") (pin "11") (pinfunction "P$3_11") (pintype "passive"))
      (node (ref "X6") (pin "2") (pinfunction "KL_2") (pintype "passive"))
    )
    (net (code "57") (name "Net-(K11-P$4)") (class "Default")
      (node (ref "K11") (pin "14") (pinfunction "P$4_14") (pintype "passive"))
      (node (ref "X6") (pin "1") (pinfunction "KL_1") (pintype "passive"))
    )
    (net (code "58") (name "Net-(K11-P$5)") (class "Default")
      (node (ref "K11") (pin "12") (pinfunction "P$5_12") (pintype "passive"))
      (node (ref "X6") (pin "3") (pinfunction "KL_3") (pintype "passive"))
    )
    (net (code "59") (name "Net-(K12-P$3)") (class "Default")
      (node (ref "K12") (pin "11") (pinfunction "P$3_11") (pintype "passive"))
      (node (ref "X7") (pin "2") (pinfunction "KL_2") (pintype "passive"))
    )
    (net (code "60") (name "Net-(K12-P$4)") (class "Default")
      (node (ref "K12") (pin "14") (pinfunction "P$4_14") (pintype "passive"))
      (node (ref "X7") (pin "1") (pinfunction "KL_1") (pintype "passive"))
    )
    (net (code "61") (name "Net-(K12-P$5)") (class "Default")
      (node (ref "K12") (pin "12") (pinfunction "P$5_12") (pintype "passive"))
      (node (ref "X7") (pin "3") (pinfunction "KL_3") (pintype "passive"))
    )
    (net (code "62") (name "Net-(LED1-PadA)") (class "Default")
      (node (ref "LED1") (pin "A") (pinfunction "A_A") (pintype "passive"))
      (node (ref "R8") (pin "2") (pinfunction "2_2") (pintype "passive"))
    )
    (net (code "63") (name "Net-(LED2-PadA)") (class "Default")
      (node (ref "LED2") (pin "A") (pinfunction "A_A") (pintype "passive"))
      (node (ref "R9") (pin "2") (pinfunction "2_2") (pintype "passive"))
    )
    (net (code "64") (name "Net-(LED3-PadA)") (class "Default")
      (node (ref "LED3") (pin "A") (pinfunction "A_A") (pintype "passive"))
      (node (ref "R10") (pin "2") (pinfunction "2_2") (pintype "passive"))
    )
    (net (code "65") (name "Net-(LED4-PadA)") (class "Default")
      (node (ref "LED4") (pin "A") (pinfunction "A_A") (pintype "passive"))
      (node (ref "R11") (pin "2") (pinfunction "2_2") (pintype "passive"))
    )
    (net (code "66") (name "Net-(LED5-PadA)") (class "Default")
      (node (ref "LED5") (pin "A") (pinfunction "A_A") (pintype "passive"))
      (node (ref "R12") (pin "2") (pinfunction "2_2") (pintype "passive"))
    )
    (net (code "67") (name "Net-(LED6-PadA)") (class "Default")
      (node (ref "LED6") (pin "A") (pinfunction "A_A") (pintype "passive"))
      (node (ref "R13") (pin "2") (pinfunction "2_2") (pintype "passive"))
    )
    (net (code "68") (name "Net-(LED7-PadA)") (class "Default")
      (node (ref "LED7") (pin "A") (pinfunction "A_A") (pintype "passive"))
      (node (ref "R14") (pin "2") (pinfunction "2_2") (pintype "passive"))
    )
    (net (code "69") (name "Net-(LED8-PadA)") (class "Default")
      (node (ref "LED8") (pin "A") (pinfunction "A_A") (pintype "passive"))
      (node (ref "R15") (pin "2") (pinfunction "2_2") (pintype "passive"))
    )
    (net (code "70") (name "Net-(LED9-PadA)") (class "Default")
      (node (ref "LED9") (pin "A") (pinfunction "A_A") (pintype "passive"))
      (node (ref "R16") (pin "2") (pinfunction "2_2") (pintype "passive"))
    )
    (net (code "71") (name "Net-(LED10-PadA)") (class "Default")
      (node (ref "LED10") (pin "A") (pinfunction "A_A") (pintype "passive"))
      (node (ref "R17") (pin "2") (pinfunction "2_2") (pintype "passive"))
    )
    (net (code "72") (name "Net-(LED11-PadA)") (class "Default")
      (node (ref "LED11") (pin "A") (pinfunction "A_A") (pintype "passive"))
      (node (ref "R18") (pin "2") (pinfunction "2_2") (pintype "passive"))
    )
    (net (code "73") (name "Net-(LED12-PadA)") (class "Default")
      (node (ref "LED12") (pin "A") (pinfunction "A_A") (pintype "passive"))
      (node (ref "R19") (pin "2") (pinfunction "2_2") (pintype "passive"))
    )
    (net (code "74") (name "Net-(LED13-PadA)") (class "Default")
      (node (ref "LED13") (pin "A") (pinfunction "A_A") (pintype "passive"))
      (node (ref "R3") (pin "2") (pinfunction "2_2") (pintype "passive"))
    )
    (net (code "75") (name "OUT1") (class "Default")
      (node (ref "IC2") (pin "15") (pinfunction "(PCINT30/OC2B/ICP)PD6_15") (pintype "bidirectional"))
      (node (ref "IC5") (pin "7") (pinfunction "I7_7") (pintype "input"))
      (node (ref "R8") (pin "1") (pinfunction "1_1") (pintype "passive"))
    )
    (net (code "76") (name "OUT2") (class "Default")
      (node (ref "IC2") (pin "16") (pinfunction "(PCINT31/OC2A)PD7_16") (pintype "bidirectional"))
      (node (ref "IC5") (pin "6") (pinfunction "I6_6") (pintype "input"))
      (node (ref "R9") (pin "1") (pinfunction "1_1") (pintype "passive"))
    )
    (net (code "77") (name "OUT3") (class "Default")
      (node (ref "IC2") (pin "21") (pinfunction "(PCINT18/TCK)PC2_21") (pintype "output"))
      (node (ref "IC5") (pin "5") (pinfunction "I5_5") (pintype "input"))
      (node (ref "R10") (pin "1") (pinfunction "1_1") (pintype "passive"))
    )
    (net (code "78") (name "OUT4") (class "Default")
      (node (ref "IC2") (pin "22") (pinfunction "(PCINT19/TMS)PC3_22") (pintype "output"))
      (node (ref "IC5") (pin "4") (pinfunction "I4_4") (pintype "input"))
      (node (ref "R11") (pin "1") (pinfunction "1_1") (pintype "passive"))
    )
    (net (code "79") (name "OUT5") (class "Default")
      (node (ref "IC2") (pin "23") (pinfunction "(PCINT20/TDO)PC4_23") (pintype "output"))
      (node (ref "IC5") (pin "3") (pinfunction "I3_3") (pintype "input"))
      (node (ref "R12") (pin "1") (pinfunction "1_1") (pintype "passive"))
    )
    (net (code "80") (name "OUT6") (class "Default")
      (node (ref "IC2") (pin "24") (pinfunction "(PCINT21/TDI)PC5_24") (pintype "output"))
      (node (ref "IC5") (pin "2") (pinfunction "I2_2") (pintype "input"))
      (node (ref "R13") (pin "1") (pinfunction "1_1") (pintype "passive"))
    )
    (net (code "81") (name "OUT7") (class "Default")
      (node (ref "IC2") (pin "25") (pinfunction "(PCINT22/TOSC1)PC6_25") (pintype "output"))
      (node (ref "IC5") (pin "1") (pinfunction "I1_1") (pintype "input"))
      (node (ref "R14") (pin "1") (pinfunction "1_1") (pintype "passive"))
    )
    (net (code "82") (name "OUT8") (class "Default")
      (node (ref "IC2") (pin "26") (pinfunction "(PCINT23/TOSC2)PC7_26") (pintype "output"))
      (node (ref "IC6") (pin "7") (pinfunction "I7_7") (pintype "input"))
      (node (ref "R15") (pin "1") (pinfunction "1_1") (pintype "passive"))
    )
    (net (code "83") (name "OUT9") (class "Default")
      (node (ref "IC2") (pin "30") (pinfunction "(PCINT7/ADC7)PA7_30") (pintype "bidirectional"))
      (node (ref "IC6") (pin "6") (pinfunction "I6_6") (pintype "input"))
      (node (ref "R16") (pin "1") (pinfunction "1_1") (pintype "passive"))
    )
    (net (code "84") (name "OUT10") (class "Default")
      (node (ref "IC2") (pin "31") (pinfunction "(PCINT6/ADC6)PA6_31") (pintype "bidirectional"))
      (node (ref "IC6") (pin "5") (pinfunction "I5_5") (pintype "input"))
      (node (ref "R17") (pin "1") (pinfunction "1_1") (pintype "passive"))
    )
    (net (code "85") (name "OUT11") (class "Default")
      (node (ref "IC2") (pin "32") (pinfunction "(PCINT5/ADC5)PA5_32") (pintype "bidirectional"))
      (node (ref "IC6") (pin "2") (pinfunction "I2_2") (pintype "input"))
      (node (ref "R18") (pin "1") (pinfunction "1_1") (pintype "passive"))
    )
    (net (code "86") (name "OUT12") (class "Default")
      (node (ref "IC2") (pin "33") (pinfunction "(PCINT4/ADC4)PA4_33") (pintype "bidirectional"))
      (node (ref "IC6") (pin "1") (pinfunction "I1_1") (pintype "input"))
      (node (ref "R19") (pin "1") (pinfunction "1_1") (pintype "passive"))
    )
    (net (code "87") (name "OUT_LED_1") (class "Default")
      (node (ref "IC2") (pin "34") (pinfunction "(PCINT3/ADC3)PA3_34") (pintype "bidirectional"))
      (node (ref "IC6") (pin "3") (pinfunction "I3_3") (pintype "input"))
    )
    (net (code "88") (name "OUT_LED_2") (class "Default")
      (node (ref "IC2") (pin "35") (pinfunction "(PCINT2/ADC2)PA2_35") (pintype "bidirectional"))
      (node (ref "IC6") (pin "4") (pinfunction "I4_4") (pintype "input"))
    )
    (net (code "89") (name "RELAIS_1") (class "Default")
      (node (ref "IC5") (pin "10") (pinfunction "O7_10") (pintype "open_collector"))
      (node (ref "K1") (pin "COIL2") (pinfunction "2_COIL2") (pintype "passive"))
    )
    (net (code "90") (name "RELAIS_2") (class "Default")
      (node (ref "IC5") (pin "11") (pinfunction "O6_11") (pintype "open_collector"))
      (node (ref "K2") (pin "COIL2") (pinfunction "2_COIL2") (pintype "passive"))
    )
    (net (code "91") (name "RELAIS_3") (class "Default")
      (node (ref "IC5") (pin "12") (pinfunction "O5_12") (pintype "open_collector"))
      (node (ref "K3") (pin "COIL2") (pinfunction "2_COIL2") (pintype "passive"))
    )
    (net (code "92") (name "RELAIS_4") (class "Default")
      (node (ref "IC5") (pin "13") (pinfunction "O4_13") (pintype "open_collector"))
      (node (ref "K4") (pin "COIL2") (pinfunction "2_COIL2") (pintype "passive"))
    )
    (net (code "93") (name "RELAIS_5") (class "Default")
      (node (ref "IC5") (pin "14") (pinfunction "O3_14") (pintype "open_collector"))
      (node (ref "K5") (pin "COIL2") (pinfunction "2_COIL2") (pintype "passive"))
    )
    (net (code "94") (name "RELAIS_6") (class "Default")
      (node (ref "IC5") (pin "15") (pinfunction "O2_15") (pintype "open_collector"))
      (node (ref "K6") (pin "COIL2") (pinfunction "2_COIL2") (pintype "passive"))
    )
    (net (code "95") (name "RELAIS_7") (class "Default")
      (node (ref "IC5") (pin "16") (pinfunction "O1_16") (pintype "open_collector"))
      (node (ref "K7") (pin "COIL2") (pinfunction "2_COIL2") (pintype "passive"))
    )
    (net (code "96") (name "RELAIS_8") (class "Default")
      (node (ref "IC6") (pin "10") (pinfunction "O7_10") (pintype "open_collector"))
      (node (ref "K8") (pin "COIL2") (pinfunction "2_COIL2") (pintype "passive"))
    )
    (net (code "97") (name "RELAIS_9") (class "Default")
      (node (ref "IC6") (pin "11") (pinfunction "O6_11") (pintype "open_collector"))
      (node (ref "K9") (pin "COIL2") (pinfunction "2_COIL2") (pintype "passive"))
    )
    (net (code "98") (name "RELAIS_10") (class "Default")
      (node (ref "IC6") (pin "12") (pinfunction "O5_12") (pintype "open_collector"))
      (node (ref "K10") (pin "COIL2") (pinfunction "2_COIL2") (pintype "passive"))
    )
    (net (code "99") (name "RELAIS_11") (class "Default")
      (node (ref "IC6") (pin "15") (pinfunction "O2_15") (pintype "open_collector"))
      (node (ref "K11") (pin "A1") (pinfunction "P$1_A1") (pintype "passive"))
    )
    (net (code "100") (name "RELAIS_12") (class "Default")
      (node (ref "IC6") (pin "16") (pinfunction "O1_16") (pintype "open_collector"))
      (node (ref "K12") (pin "A1") (pinfunction "P$1_A1") (pintype "passive"))
    )
    (net (code "101") (name "RST") (class "Default")
      (node (ref "IC2") (pin "4") (pinfunction "RESET_4") (pintype "input"))
      (node (ref "ISP") (pin "RST") (pinfunction "RST_RST") (pintype "passive"))
      (node (ref "R1") (pin "1") (pinfunction "1_1") (pintype "passive"))
      (node (ref "S1") (pin "3") (pinfunction "S_3") (pintype "passive"))
      (node (ref "S1") (pin "4") (pinfunction "S1_4") (pintype "passive"))
    )
    (net (code "102") (name "RXCAN") (class "Default")
      (node (ref "IC3") (pin "2") (pinfunction "RXCAN_2") (pintype "input"))
      (node (ref "IC4") (pin "4") (pinfunction "RXD_4") (pintype "output"))
    )
    (net (code "103") (name "SCK") (class "Default")
      (node (ref "IC2") (pin "3") (pinfunction "(PCINT15/SCK)PB7_3") (pintype "bidirectional"))
      (node (ref "IC3") (pin "13") (pinfunction "SCK_13") (pintype "input"))
      (node (ref "ISP") (pin "SCK") (pinfunction "SCK_SCK") (pintype "passive"))
    )
    (net (code "104") (name "SCL") (class "Default")
      (node (ref "IC2") (pin "19") (pinfunction "(PCINT16/SCL)PC0_19") (pintype "output"))
      (node (ref "IC7") (pin "14") (pinfunction "SCL_14") (pintype "input"))
      (node (ref "IC8") (pin "14") (pinfunction "SCL_14") (pintype "input"))
      (node (ref "IC9") (pin "14") (pinfunction "SCL_14") (pintype "input"))
      (node (ref "R6") (pin "1") (pinfunction "1_1") (pintype "passive"))
      (node (ref "X12") (pin "4") (pinfunction "S_4") (pintype "passive"))
    )
    (net (code "105") (name "SDA") (class "Default")
      (node (ref "IC2") (pin "20") (pinfunction "(PCINT17/SDA)PC1_20") (pintype "output"))
      (node (ref "IC7") (pin "15") (pinfunction "SDA_15") (pintype "bidirectional"))
      (node (ref "IC8") (pin "15") (pinfunction "SDA_15") (pintype "bidirectional"))
      (node (ref "IC9") (pin "15") (pinfunction "SDA_15") (pintype "bidirectional"))
      (node (ref "R5") (pin "1") (pinfunction "1_1") (pintype "passive"))
      (node (ref "X12") (pin "3") (pinfunction "S_3") (pintype "passive"))
    )
    (net (code "106") (name "TXCAN") (class "Default")
      (node (ref "IC3") (pin "1") (pinfunction "TXCAN_1") (pintype "output"))
      (node (ref "IC4") (pin "1") (pinfunction "TXD_1") (pintype "input"))
    )
    (net (code "107") (name "unconnected-(IC2-(PCINT0{slash}ADC0)PA0-Pad37)") (class "Default")
      (node (ref "IC2") (pin "37") (pinfunction "(PCINT0/ADC0)PA0_37") (pintype "bidirectional"))
    )
    (net (code "108") (name "unconnected-(IC2-(PCINT8{slash}XCK0{slash}T0)PB0-Pad40)") (class "Default")
      (node (ref "IC2") (pin "40") (pinfunction "(PCINT8/XCK0/T0)PB0_40") (pintype "bidirectional"))
    )
    (net (code "109") (name "unconnected-(IC2-(PCINT9{slash}CLKO{slash}T1)PB1-Pad41)") (class "Default")
      (node (ref "IC2") (pin "41") (pinfunction "(PCINT9/CLKO/T1)PB1_41") (pintype "bidirectional"))
    )
    (net (code "110") (name "unconnected-(IC2-(PCINT10{slash}INT2{slash}AIN0)PB2-Pad42)") (class "Default")
      (node (ref "IC2") (pin "42") (pinfunction "(PCINT10/INT2/AIN0)PB2_42") (pintype "bidirectional"))
    )
    (net (code "111") (name "unconnected-(IC2-(PCINT11{slash}OC0A{slash}AIN1)PB3-Pad43)") (class "Default")
      (node (ref "IC2") (pin "43") (pinfunction "(PCINT11/OC0A/AIN1)PB3_43") (pintype "bidirectional"))
    )
    (net (code "112") (name "unconnected-(IC2-(PCINT24{slash}RXD0)PD0-Pad9)") (class "Default")
      (node (ref "IC2") (pin "9") (pinfunction "(PCINT24/RXD0)PD0_9") (pintype "bidirectional"))
    )
    (net (code "113") (name "unconnected-(IC2-(PCINT25{slash}TXD0)PD1-Pad10)") (class "Default")
      (node (ref "IC2") (pin "10") (pinfunction "(PCINT25/TXD0)PD1_10") (pintype "bidirectional"))
    )
    (net (code "114") (name "unconnected-(IC2-(PCINT28{slash}OC1B)PD4-Pad13)") (class "Default")
      (node (ref "IC2") (pin "13") (pinfunction "(PCINT28/OC1B)PD4_13") (pintype "bidirectional"))
    )
    (net (code "115") (name "unconnected-(IC2-AREF-Pad29)") (class "Default")
      (node (ref "IC2") (pin "29") (pinfunction "AREF_29") (pintype "passive"))
    )
    (net (code "116") (name "unconnected-(IC3-CLKOUT-Pad3)") (class "Default")
      (node (ref "IC3") (pin "3") (pinfunction "CLKOUT_3") (pintype "output"))
    )
    (net (code "117") (name "unconnected-(IC3-RX0BF-Pad11)") (class "Default")
      (node (ref "IC3") (pin "11") (pinfunction "RX0BF_11") (pintype "output"))
    )
    (net (code "118") (name "unconnected-(IC3-RX1BF-Pad10)") (class "Default")
      (node (ref "IC3") (pin "10") (pinfunction "RX1BF_10") (pintype "output"))
    )
    (net (code "119") (name "unconnected-(IC3-TX0RTS-Pad4)") (class "Default")
      (node (ref "IC3") (pin "4") (pinfunction "TX0RTS_4") (pintype "input"))
    )
    (net (code "120") (name "unconnected-(IC3-TX1RTS-Pad5)") (class "Default")
      (node (ref "IC3") (pin "5") (pinfunction "TX1RTS_5") (pintype "input"))
    )
    (net (code "121") (name "unconnected-(IC3-TX2RTS-Pad6)") (class "Default")
      (node (ref "IC3") (pin "6") (pinfunction "TX2RTS_6") (pintype "input"))
    )
    (net (code "122") (name "unconnected-(K1B-O-PadCON2OPTION)") (class "Default")
      (node (ref "K1") (pin "CON2OPTION") (pinfunction "O_CON2OPTION") (pintype "passive"))
    )
    (net (code "123") (name "unconnected-(K2B-O-PadCON2OPTION)") (class "Default")
      (node (ref "K2") (pin "CON2OPTION") (pinfunction "O_CON2OPTION") (pintype "passive"))
    )
    (net (code "124") (name "unconnected-(K3B-O-PadCON2OPTION)") (class "Default")
      (node (ref "K3") (pin "CON2OPTION") (pinfunction "O_CON2OPTION") (pintype "passive"))
    )
    (net (code "125") (name "unconnected-(K4B-O-PadCON2OPTION)") (class "Default")
      (node (ref "K4") (pin "CON2OPTION") (pinfunction "O_CON2OPTION") (pintype "passive"))
    )
    (net (code "126") (name "unconnected-(K5B-O-PadCON2OPTION)") (class "Default")
      (node (ref "K5") (pin "CON2OPTION") (pinfunction "O_CON2OPTION") (pintype "passive"))
    )
    (net (code "127") (name "unconnected-(K6B-O-PadCON2OPTION)") (class "Default")
      (node (ref "K6") (pin "CON2OPTION") (pinfunction "O_CON2OPTION") (pintype "passive"))
    )
    (net (code "128") (name "unconnected-(K7B-O-PadCON2OPTION)") (class "Default")
      (node (ref "K7") (pin "CON2OPTION") (pinfunction "O_CON2OPTION") (pintype "passive"))
    )
    (net (code "129") (name "unconnected-(K8B-O-PadCON2OPTION)") (class "Default")
      (node (ref "K8") (pin "CON2OPTION") (pinfunction "O_CON2OPTION") (pintype "passive"))
    )
    (net (code "130") (name "unconnected-(K9B-O-PadCON2OPTION)") (class "Default")
      (node (ref "K9") (pin "CON2OPTION") (pinfunction "O_CON2OPTION") (pintype "passive"))
    )
    (net (code "131") (name "unconnected-(K10B-O-PadCON2OPTION)") (class "Default")
      (node (ref "K10") (pin "CON2OPTION") (pinfunction "O_CON2OPTION") (pintype "passive"))
    )
  )
)
